# Scheme.net
KiCad netlist of a schematic drawn in Altium Designer
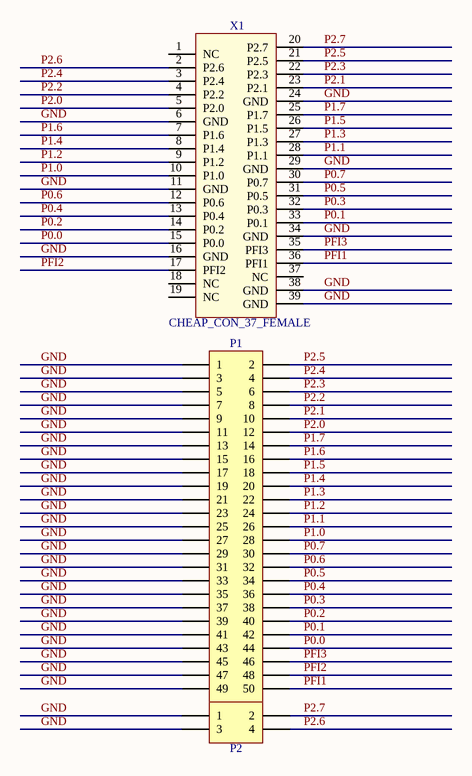
[diagram p0: Scheme.SchDoc]

(export (version "E")
  (design (tool "Eeschema 10.0.6"))
  (components
    (comp (ref "P1")
      (value "Header 25X2")
      (footprint "HDR2X25")
      (description "Header, 25-Pin, Dual row")
      (fields (field (name "PUBLISHER") "Altium Limited"))
      (libsource (lib "Miscellaneous Connectors") (part "Header 25X2"))
    )
    (comp (ref "P2")
      (value "Header 2X2")
      (footprint "HDR2X2")
      (description "Header, 2-Pin, Dual row")
      (fields (field (name "PUBLISHER") "Altium Limited"))
      (libsource (lib "Miscellaneous Connectors") (part "Header 2X2"))
    )
    (comp (ref "X1")
      (value "CHEAP_CON_37_FEMALE")
      (footprint "CHEAP_CONN_FEMALE")
      (libsource (lib "Schlib") (part "CHEAP_CON_37_FEMALE"))
    )
  )
  (nets
    (net (code "1") (name "/GND") (class "Default")
      (node (ref "P1") (pin "1") (pinfunction "1_1") (pintype "passive"))
      (node (ref "P1") (pin "11") (pinfunction "11_11") (pintype "passive"))
      (node (ref "P1") (pin "13") (pinfunction "13_13") (pintype "passive"))
      (node (ref "P1") (pin "15") (pinfunction "15_15") (pintype "passive"))
      (node (ref "P1") (pin "17") (pinfunction "17_17") (pintype "passive"))
      (node (ref "P1") (pin "19") (pinfunction "19_19") (pintype "passive"))
      (node (ref "P1") (pin "21") (pinfunction "21_21") (pintype "passive"))
      (node (ref "P1") (pin "23") (pinfunction "23_23") (pintype "passive"))
      (node (ref "P1") (pin "25") (pinfunction "25_25") (pintype "passive"))
      (node (ref "P1") (pin "27") (pinfunction "27_27") (pintype "passive"))
      (node (ref "P1") (pin "29") (pinfunction "29_29") (pintype "passive"))
      (node (ref "P1") (pin "3") (pinfunction "3_3") (pintype "passive"))
      (node (ref "P1") (pin "31") (pinfunction "31_31") (pintype "passive"))
      (node (ref "P1") (pin "33") (pinfunction "33_33") (pintype "passive"))
      (node (ref "P1") (pin "35") (pinfunction "35_35") (pintype "passive"))
      (node (ref "P1") (pin "37") (pinfunction "37_37") (pintype "passive"))
      (node (ref "P1") (pin "39") (pinfunction "39_39") (pintype "passive"))
      (node (ref "P1") (pin "41") (pinfunction "41_41") (pintype "passive"))
      (node (ref "P1") (pin "43") (pinfunction "43_43") (pintype "passive"))
      (node (ref "P1") (pin "45") (pinfunction "45_45") (pintype "passive"))
      (node (ref "P1") (pin "47") (pinfunction "47_47") (pintype "passive"))
      (node (ref "P1") (pin "49") (pinfunction "49_49") (pintype "passive"))
      (node (ref "P1") (pin "5") (pinfunction "5_5") (pintype "passive"))
      (node (ref "P1") (pin "7") (pinfunction "7_7") (pintype "passive"))
      (node (ref "P1") (pin "9") (pinfunction "9_9") (pintype "passive"))
      (node (ref "P2") (pin "1") (pinfunction "1_1") (pintype "passive"))
      (node (ref "P2") (pin "3") (pinfunction "3_3") (pintype "passive"))
      (node (ref "X1") (pin "11") (pinfunction "GND_11") (pintype "passive"))
      (node (ref "X1") (pin "16") (pinfunction "GND_16") (pintype "passive"))
      (node (ref "X1") (pin "24") (pinfunction "GND_24") (pintype "passive"))
      (node (ref "X1") (pin "29") (pinfunction "GND_29") (pintype "passive"))
      (node (ref "X1") (pin "34") (pinfunction "GND_34") (pintype "passive"))
      (node (ref "X1") (pin "38") (pinfunction "GND_38") (pintype "passive"))
      (node (ref "X1") (pin "39") (pinfunction "GND_39") (pintype "passive"))
      (node (ref "X1") (pin "6") (pinfunction "GND_6") (pintype "passive"))
    )
    (net (code "2") (name "/P0.0") (class "Default")
      (node (ref "P1") (pin "44") (pinfunction "44_44") (pintype "passive"))
      (node (ref "X1") (pin "15") (pinfunction "P0.0_15") (pintype "passive"))
    )
    (net (code "3") (name "/P0.1") (class "Default")
      (node (ref "P1") (pin "42") (pinfunction "42_42") (pintype "passive"))
      (node (ref "X1") (pin "33") (pinfunction "P0.1_33") (pintype "passive"))
    )
    (net (code "4") (name "/P0.2") (class "Default")
      (node (ref "P1") (pin "40") (pinfunction "40_40") (pintype "passive"))
      (node (ref "X1") (pin "14") (pinfunction "P0.2_14") (pintype "passive"))
    )
    (net (code "5") (name "/P0.3") (class "Default")
      (node (ref "P1") (pin "38") (pinfunction "38_38") (pintype "passive"))
      (node (ref "X1") (pin "32") (pinfunction "P0.3_32") (pintype "passive"))
    )
    (net (code "6") (name "/P0.4") (class "Default")
      (node (ref "P1") (pin "36") (pinfunction "36_36") (pintype "passive"))
      (node (ref "X1") (pin "13") (pinfunction "P0.4_13") (pintype "passive"))
    )
    (net (code "7") (name "/P0.5") (class "Default")
      (node (ref "P1") (pin "34") (pinfunction "34_34") (pintype "passive"))
      (node (ref "X1") (pin "31") (pinfunction "P0.5_31") (pintype "passive"))
    )
    (net (code "8") (name "/P0.6") (class "Default")
      (node (ref "P1") (pin "32") (pinfunction "32_32") (pintype "passive"))
      (node (ref "X1") (pin "12") (pinfunction "P0.6_12") (pintype "passive"))
    )
    (net (code "9") (name "/P0.7") (class "Default")
      (node (ref "P1") (pin "30") (pinfunction "30_30") (pintype "passive"))
      (node (ref "X1") (pin "30") (pinfunction "P0.7_30") (pintype "passive"))
    )
    (net (code "10") (name "/P1.0") (class "Default")
      (node (ref "P1") (pin "28") (pinfunction "28_28") (pintype "passive"))
      (node (ref "X1") (pin "10") (pinfunction "P1.0_10") (pintype "passive"))
    )
    (net (code "11") (name "/P1.1") (class "Default")
      (node (ref "P1") (pin "26") (pinfunction "26_26") (pintype "passive"))
      (node (ref "X1") (pin "28") (pinfunction "P1.1_28") (pintype "passive"))
    )
    (net (code "12") (name "/P1.2") (class "Default")
      (node (ref "P1") (pin "24") (pinfunction "24_24") (pintype "passive"))
      (node (ref "X1") (pin "9") (pinfunction "P1.2_9") (pintype "passive"))
    )
    (net (code "13") (name "/P1.3") (class "Default")
      (node (ref "P1") (pin "22") (pinfunction "22_22") (pintype "passive"))
      (node (ref "X1") (pin "27") (pinfunction "P1.3_27") (pintype "passive"))
    )
    (net (code "14") (name "/P1.4") (class "Default")
      (node (ref "P1") (pin "20") (pinfunction "20_20") (pintype "passive"))
      (node (ref "X1") (pin "8") (pinfunction "P1.4_8") (pintype "passive"))
    )
    (net (code "15") (name "/P1.5") (class "Default")
      (node (ref "P1") (pin "18") (pinfunction "18_18") (pintype "passive"))
      (node (ref "X1") (pin "26") (pinfunction "P1.5_26") (pintype "passive"))
    )
    (net (code "16") (name "/P1.6") (class "Default")
      (node (ref "P1") (pin "16") (pinfunction "16_16") (pintype "passive"))
      (node (ref "X1") (pin "7") (pinfunction "P1.6_7") (pintype "passive"))
    )
    (net (code "17") (name "/P1.7") (class "Default")
      (node (ref "P1") (pin "14") (pinfunction "14_14") (pintype "passive"))
      (node (ref "X1") (pin "25") (pinfunction "P1.7_25") (pintype "passive"))
    )
    (net (code "18") (name "/P2.0") (class "Default")
      (node (ref "P1") (pin "12") (pinfunction "12_12") (pintype "passive"))
      (node (ref "X1") (pin "5") (pinfunction "P2.0_5") (pintype "passive"))
    )
    (net (code "19") (name "/P2.1") (class "Default")
      (node (ref "P1") (pin "10") (pinfunction "10_10") (pintype "passive"))
      (node (ref "X1") (pin "23") (pinfunction "P2.1_23") (pintype "passive"))
    )
    (net (code "20") (name "/P2.2") (class "Default")
      (node (ref "P1") (pin "8") (pinfunction "8_8") (pintype "passive"))
      (node (ref "X1") (pin "4") (pinfunction "P2.2_4") (pintype "passive"))
    )
    (net (code "21") (name "/P2.3") (class "Default")
      (node (ref "P1") (pin "6") (pinfunction "6_6") (pintype "passive"))
      (node (ref "X1") (pin "22") (pinfunction "P2.3_22") (pintype "passive"))
    )
    (net (code "22") (name "/P2.4") (class "Default")
      (node (ref "P1") (pin "4") (pinfunction "4_4") (pintype "passive"))
      (node (ref "X1") (pin "3") (pinfunction "P2.4_3") (pintype "passive"))
    )
    (net (code "23") (name "/P2.5") (class "Default")
      (node (ref "P1") (pin "2") (pinfunction "2_2") (pintype "passive"))
      (node (ref "X1") (pin "21") (pinfunction "P2.5_21") (pintype "passive"))
    )
    (net (code "24") (name "/P2.6") (class "Default")
      (node (ref "P2") (pin "4") (pinfunction "4_4") (pintype "passive"))
      (node (ref "X1") (pin "2") (pinfunction "P2.6_2") (pintype "passive"))
    )
    (net (code "25") (name "/P2.7") (class "Default")
      (node (ref "P2") (pin "2") (pinfunction "2_2") (pintype "passive"))
      (node (ref "X1") (pin "20") (pinfunction "P2.7_20") (pintype "passive"))
    )
    (net (code "26") (name "/PFI1") (class "Default")
      (node (ref "P1") (pin "50") (pinfunction "50_50") (pintype "passive"))
      (node (ref "X1") (pin "36") (pinfunction "PFI1_36") (pintype "passive"))
    )
    (net (code "27") (name "/PFI2") (class "Default")
      (node (ref "P1") (pin "48") (pinfunction "48_48") (pintype "passive"))
      (node (ref "X1") (pin "17") (pinfunction "PFI2_17") (pintype "passive"))
    )
    (net (code "28") (name "/PFI3") (class "Default")
      (node (ref "P1") (pin "46") (pinfunction "46_46") (pintype "passive"))
      (node (ref "X1") (pin "35") (pinfunction "PFI3_35") (pintype "passive"))
    )
    (net (code "29") (name "unconnected-(X1-NC-Pad1)") (class "Default")
      (node (ref "X1") (pin "1") (pinfunction "NC_1") (pintype "passive"))
    )
    (net (code "30") (name "unconnected-(X1-NC-Pad18)") (class "Default")
      (node (ref "X1") (pin "18") (pinfunction "NC_18") (pintype "passive"))
    )
    (net (code "31") (name "unconnected-(X1-NC-Pad19)") (class "Default")
      (node (ref "X1") (pin "19") (pinfunction "NC_19") (pintype "passive"))
    )
    (net (code "32") (name "unconnected-(X1-NC-Pad37)") (class "Default")
      (node (ref "X1") (pin "37") (pinfunction "NC_37") (pintype "passive"))
    )
  )
)
